# design.net
KiCad netlist of a schematic drawn in EasyEDA Pro
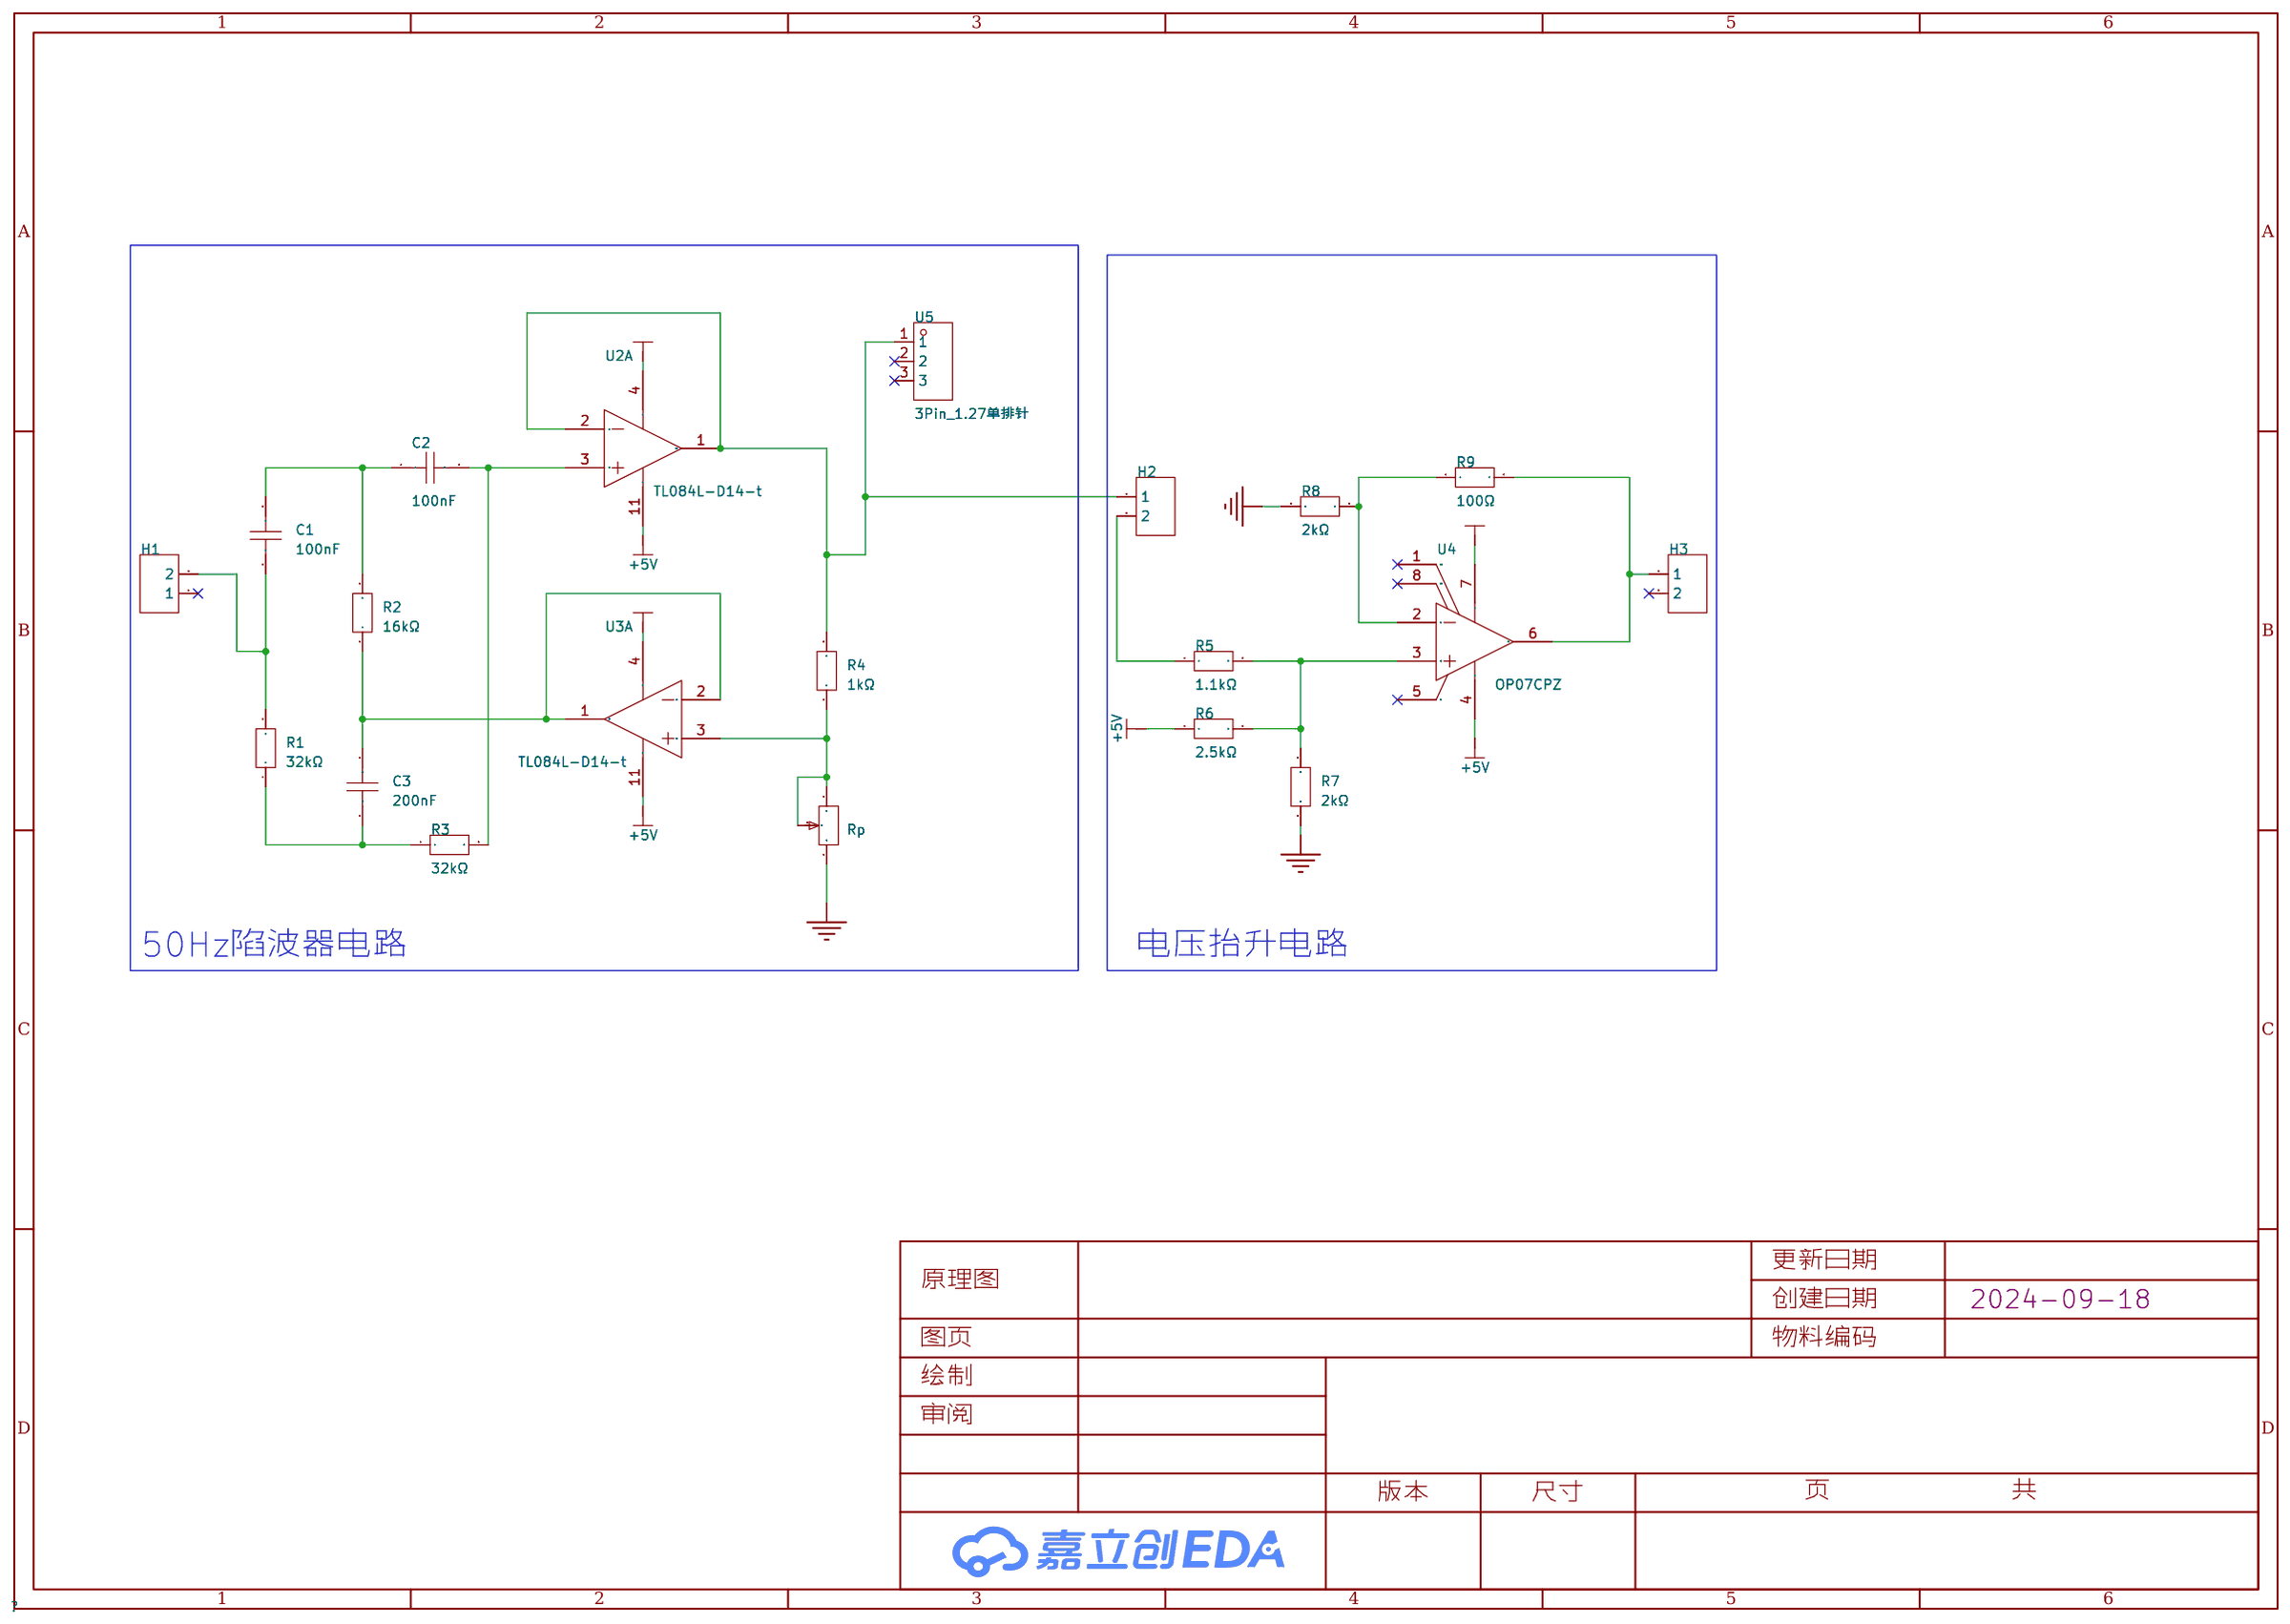
[diagram p0: schematic sheet]

(export (version "E")
  (design (tool "Eeschema 10.0.6"))
  (components
    (comp (ref "C1")
      (value "100nF")
      (footprint "easyedapro:CAP-TH_L5.1-W3.8-P5.08-D1.2")
      (description "容值:100nF;精度:±10%;额定电压:630V;温度系数:X7R;")
      (fields (field (name "Manufacturer Part") "C322C104KBR5TA") (field (name "Manufacturer") "KEMET(基美)"))
      (libsource (lib "easyedapro") (part "C322C104KBR5TA"))
    )
    (comp (ref "C2")
      (value "100nF")
      (footprint "easyedapro:CAP-TH_L5.1-W3.8-P5.08-D1.2")
      (description "容值:100nF;精度:±10%;额定电压:630V;温度系数:X7R;")
      (fields (field (name "Manufacturer Part") "C322C104KBR5TA") (field (name "Manufacturer") "KEMET(基美)"))
      (libsource (lib "easyedapro") (part "C322C104KBR5TA"))
    )
    (comp (ref "C3")
      (value "200nF")
      (footprint "easyedapro:CAP-TH_L18.0-W8.0-P15.00-D0.8")
      (description "容值:200nF;精度:±20%;电压(AC):305V;等级:X2;")
      (fields (field (name "Manufacturer Part") "B32922H3204M") (field (name "Manufacturer") "TDK"))
      (libsource (lib "easyedapro") (part "B32922H3204M"))
    )
    (comp (ref "H1")
      (value "~")
      (footprint "easyedapro:HDR-TH_2P-P2.54-V-F")
      (libsource (lib "easyedapro") (part "Header-Female-2.54_1x2"))
    )
    (comp (ref "H2")
      (value "~")
      (footprint "easyedapro:HDR-TH_2P-P2.54-V-F")
      (libsource (lib "easyedapro") (part "Header-Female-2.54_1x2"))
    )
    (comp (ref "H3")
      (value "~")
      (footprint "easyedapro:HDR-TH_2P-P2.54-V-F")
      (libsource (lib "easyedapro") (part "Header-Female-2.54_1x2"))
    )
    (comp (ref "R1")
      (value "32kΩ")
      (footprint "easyedapro:RES-TH_BD2.4-L6.5-P10.50-D0.5")
      (description "电阻类型:金属膜电阻;阻值:32kΩ;精度:±0.1%;功率:250mW;温度系数:±25ppm/°C;")
      (fields
        (field (name "Manufacturer Part") "RNF14BTE32K0")
        (field (name "Manufacturer") "SEI(Stackpole Electronics Inc.)")
      )
      (libsource (lib "easyedapro") (part "RNF14BTE32K0"))
    )
    (comp (ref "R2")
      (value "16kΩ")
      (footprint "easyedapro:RES-TH_BD3.3-L9.0-P13.00-D0.6")
      (description "电阻类型:金属膜电阻;阻值:16kΩ;精度:±5%;功率:500mW;温度系数:±300ppm/°C;")
      (fields (field (name "Manufacturer Part") "RSF-50JT-52-16K") (field (name "Manufacturer") "YAGEO(国巨)"))
      (libsource (lib "easyedapro") (part "RSF-50JT-52-16K"))
    )
    (comp (ref "R3")
      (value "32kΩ")
      (footprint "easyedapro:RES-TH_BD2.4-L6.5-P10.50-D0.5")
      (description "电阻类型:金属膜电阻;阻值:32kΩ;精度:±0.1%;功率:250mW;温度系数:±25ppm/°C;")
      (fields
        (field (name "Manufacturer Part") "RNF14BTE32K0")
        (field (name "Manufacturer") "SEI(Stackpole Electronics Inc.)")
      )
      (libsource (lib "easyedapro") (part "RNF14BTE32K0"))
    )
    (comp (ref "R4")
      (value "1kΩ")
      (footprint "easyedapro:RES-TH_BD2.3-L6.5-P10.50-D0.5")
      (description "电阻类型:金属膜电阻;阻值:5.1kΩ;精度:±1%;功率:250mW;温度系数:±200ppm/°C;")
      (fields (field (name "Manufacturer Part") "MF1/4W-5.1KΩ±1%T52") (field (name "Manufacturer") "华星机电"))
      (libsource (lib "easyedapro") (part "MF1/4W-5.1KΩ±1%T52"))
    )
    (comp (ref "R5")
      (value "1.1kΩ")
      (footprint "easyedapro:RES-TH_BD3.3-L9.0-P13.00-D0.6")
      (description "电阻类型:金属膜电阻;阻值:1.1kΩ;精度:±5%;功率:500mW;温度系数:±300ppm/°C;")
      (fields (field (name "Manufacturer Part") "RSF-50JR-52-1K1") (field (name "Manufacturer") "YAGEO(国巨)"))
      (libsource (lib "easyedapro") (part "RSF-50JR-52-1K1"))
    )
    (comp (ref "R6")
      (value "2.5kΩ")
      (footprint "easyedapro:RES-TH_BD4.6-L11.4-P15.40-D0.8")
      (description "电阻类型:绕线电阻;阻值:2.5kΩ;精度:±1%;功率:2W;温度系数:±20ppm/°C;")
      (fields (field (name "Manufacturer Part") "WHC2K5FET") (field (name "Manufacturer") "Ohmite"))
      (libsource (lib "easyedapro") (part "WHC2K5FET"))
    )
    (comp (ref "R7")
      (value "2kΩ")
      (footprint "easyedapro:RES-TH_BD2.3-L6.5-P10.50-D0.5")
      (description "电阻类型:金属膜电阻;阻值:2kΩ;精度:±1%;功率:250mW;温度系数:±200ppm/°C;")
      (fields (field (name "Manufacturer Part") "MF1/4W-2KΩ±1%T52") (field (name "Manufacturer") "华星机电"))
      (libsource (lib "easyedapro") (part "MF1/4W-2KΩ±1%T52"))
    )
    (comp (ref "R8")
      (value "2kΩ")
      (footprint "easyedapro:RES-TH_BD2.3-L6.5-P10.50-D0.5")
      (description "电阻类型:金属膜电阻;阻值:2kΩ;精度:±1%;功率:250mW;温度系数:±200ppm/°C;")
      (fields (field (name "Manufacturer Part") "MF1/4W-2KΩ±1%T52") (field (name "Manufacturer") "华星机电"))
      (libsource (lib "easyedapro") (part "MF1/4W-2KΩ±1%T52"))
    )
    (comp (ref "R9")
      (value "100Ω")
      (footprint "easyedapro:RES-TH_BD3.7-L10.0-P15.00-D0.6")
      (description "电阻类型:金属膜电阻;阻值:100Ω;精度:±0.1%;功率:500mW;温度系数:±5ppm/°C;")
      (fields (field (name "Manufacturer Part") "MMFR3710B100RV9") (field (name "Manufacturer") "RESI(开步睿思)"))
      (libsource (lib "easyedapro") (part "MMFR3710B100RV9"))
    )
    (comp (ref "Rp")
      (value "-")
      (footprint "easyedapro:RES-ADJ-TH_3296W")
      (description "阻值:-;功率:-;")
      (fields (field (name "Manufacturer Part") "精密电位器 3296W/50欧姆"))
      (libsource (lib "easyedapro") (part "Precision potentiometer 3296W/50ohm"))
    )
    (comp (ref "U2")
      (value "TL084L-D14-t")
      (footprint "easyedapro:PDIP-14_L19.3-W6.5-P2.54-LS7.6-BL")
      (fields (field (name "Manufacturer") "UTC(友顺)"))
      (libsource (lib "easyedapro") (part "TL084L"))
    )
    (comp (ref "U3")
      (value "TL084L-D14-t")
      (footprint "easyedapro:PDIP-14_L19.3-W6.5-P2.54-LS7.6-BL")
      (fields (field (name "Manufacturer") "UTC(友顺)"))
      (libsource (lib "easyedapro") (part "TL084L"))
    )
    (comp (ref "U4")
      (value "OP07CPZ")
      (footprint "easyedapro:PDIP-8_L9.3-W6.4-P2.54-LS7.6-BL")
      (description "超低失调电压运算放大器")
      (fields (field (name "Manufacturer") "ADI(亚德诺)"))
      (libsource (lib "easyedapro") (part "OP07CPZ"))
    )
    (comp (ref "U5")
      (value "3Pin_1.27单排针")
      (footprint "easyedapro:HDR-TH_3P-P1.27-V-M-A")
      (libsource (lib "easyedapro") (part "3PIN_1.27单排针"))
    )
  )
  (nets
    (net (code "1") (name "+5V") (class "Default")
      (node (ref "R6") (pin "1") (pinfunction "1_1") (pintype "unspecified"))
      (node (ref "U2") (pin "11") (pinfunction "V-_11") (pintype "unspecified"))
      (node (ref "U3") (pin "11") (pinfunction "V-_11") (pintype "unspecified"))
      (node (ref "U4") (pin "4") (pinfunction "V-_4") (pintype "unspecified"))
    )
    (net (code "2") (name "-5V") (class "Default")
      (node (ref "U2") (pin "4") (pinfunction "V+_4") (pintype "unspecified"))
      (node (ref "U3") (pin "4") (pinfunction "V+_4") (pintype "unspecified"))
      (node (ref "U4") (pin "7") (pinfunction "V+_7") (pintype "unspecified"))
    )
    (net (code "3") (name "GND") (class "Default")
      (node (ref "R7") (pin "1") (pinfunction "1_1") (pintype "unspecified"))
      (node (ref "R8") (pin "1") (pinfunction "1_1") (pintype "unspecified"))
      (node (ref "Rp") (pin "3") (pinfunction "3_3") (pintype "input"))
    )
    (net (code "4") (name "Net-(C1-Pad1)") (class "Default")
      (node (ref "C1") (pin "1") (pinfunction "1_1") (pintype "unspecified"))
      (node (ref "H1") (pin "2") (pinfunction "2_2") (pintype "input"))
      (node (ref "R1") (pin "2") (pinfunction "2_2") (pintype "unspecified"))
    )
    (net (code "5") (name "Net-(C1-Pad2)") (class "Default")
      (node (ref "C1") (pin "2") (pinfunction "2_2") (pintype "unspecified"))
      (node (ref "C2") (pin "1") (pinfunction "1_1") (pintype "unspecified"))
      (node (ref "R2") (pin "2") (pinfunction "2_2") (pintype "unspecified"))
    )
    (net (code "6") (name "Net-(C3-Pad1)") (class "Default")
      (node (ref "C3") (pin "1") (pinfunction "1_1") (pintype "unspecified"))
      (node (ref "R1") (pin "1") (pinfunction "1_1") (pintype "unspecified"))
      (node (ref "R3") (pin "1") (pinfunction "1_1") (pintype "unspecified"))
    )
    (net (code "7") (name "Net-(H2-Pad2)") (class "Default")
      (node (ref "H2") (pin "2") (pinfunction "2_2") (pintype "input"))
      (node (ref "R5") (pin "1") (pinfunction "1_1") (pintype "input"))
    )
    (net (code "8") (name "Net-(U2A-IN1+)") (class "Default")
      (node (ref "C2") (pin "2") (pinfunction "2_2") (pintype "unspecified"))
      (node (ref "R3") (pin "2") (pinfunction "2_2") (pintype "unspecified"))
      (node (ref "U2") (pin "3") (pinfunction "IN1+_3") (pintype "unspecified"))
    )
    (net (code "9") (name "Net-(U2A-IN1-)") (class "Default")
      (node (ref "H2") (pin "1") (pinfunction "1_1") (pintype "input"))
      (node (ref "R4") (pin "2") (pinfunction "2_2") (pintype "unspecified"))
      (node (ref "U2") (pin "1") (pinfunction "OUT1_1") (pintype "output"))
      (node (ref "U2") (pin "2") (pinfunction "IN1-_2") (pintype "unspecified"))
      (node (ref "U5") (pin "1") (pinfunction "1_1") (pintype "unspecified"))
    )
    (net (code "10") (name "Net-(U3A-IN1+)") (class "Default")
      (node (ref "R4") (pin "1") (pinfunction "1_1") (pintype "unspecified"))
      (node (ref "Rp") (pin "1") (pinfunction "1_1") (pintype "input"))
      (node (ref "Rp") (pin "2") (pinfunction "2_2") (pintype "input"))
      (node (ref "U3") (pin "3") (pinfunction "IN1+_3") (pintype "unspecified"))
    )
    (net (code "11") (name "Net-(U3A-IN1-)") (class "Default")
      (node (ref "C3") (pin "2") (pinfunction "2_2") (pintype "unspecified"))
      (node (ref "R2") (pin "1") (pinfunction "1_1") (pintype "unspecified"))
      (node (ref "U3") (pin "1") (pinfunction "OUT1_1") (pintype "output"))
      (node (ref "U3") (pin "2") (pinfunction "IN1-_2") (pintype "unspecified"))
    )
    (net (code "12") (name "Net-(U4-IN+)") (class "Default")
      (node (ref "R5") (pin "2") (pinfunction "2_2") (pintype "input"))
      (node (ref "R6") (pin "2") (pinfunction "2_2") (pintype "unspecified"))
      (node (ref "R7") (pin "2") (pinfunction "2_2") (pintype "unspecified"))
      (node (ref "U4") (pin "3") (pinfunction "IN+_3") (pintype "unspecified"))
    )
    (net (code "13") (name "Net-(U4-IN-)") (class "Default")
      (node (ref "R8") (pin "2") (pinfunction "2_2") (pintype "unspecified"))
      (node (ref "R9") (pin "1") (pinfunction "1_1") (pintype "unspecified"))
      (node (ref "U4") (pin "2") (pinfunction "IN-_2") (pintype "unspecified"))
    )
    (net (code "14") (name "Net-(U4-OUT)") (class "Default")
      (node (ref "H3") (pin "1") (pinfunction "1_1") (pintype "input"))
      (node (ref "R9") (pin "2") (pinfunction "2_2") (pintype "unspecified"))
      (node (ref "U4") (pin "6") (pinfunction "OUT_6") (pintype "output"))
    )
    (net (code "15") (name "unconnected-(H1-Pad1)") (class "Default")
      (node (ref "H1") (pin "1") (pinfunction "1_1") (pintype "input+no_connect"))
    )
    (net (code "16") (name "unconnected-(H3-Pad2)") (class "Default")
      (node (ref "H3") (pin "2") (pinfunction "2_2") (pintype "input+no_connect"))
    )
    (net (code "17") (name "unconnected-(U4-NC-Pad5)") (class "Default")
      (node (ref "U4") (pin "5") (pinfunction "NC_5") (pintype "unspecified+no_connect"))
    )
    (net (code "18") (name "unconnected-(U4-VOS_TRIM-Pad1)") (class "Default")
      (node (ref "U4") (pin "1") (pinfunction "VOS_TRIM_1") (pintype "unspecified+no_connect"))
    )
    (net (code "19") (name "unconnected-(U4-VOS_TRIM-Pad8)") (class "Default")
      (node (ref "U4") (pin "8") (pinfunction "VOS_TRIM_8") (pintype "unspecified+no_connect"))
    )
    (net (code "20") (name "unconnected-(U5-Pad2)") (class "Default")
      (node (ref "U5") (pin "2") (pinfunction "2_2") (pintype "unspecified+no_connect"))
    )
    (net (code "21") (name "unconnected-(U5-Pad3)") (class "Default")
      (node (ref "U5") (pin "3") (pinfunction "3_3") (pintype "unspecified+no_connect"))
    )
  )
)
